# 20_V2X_MODEM.net
KiCad netlist of a schematic drawn in Altium Designer
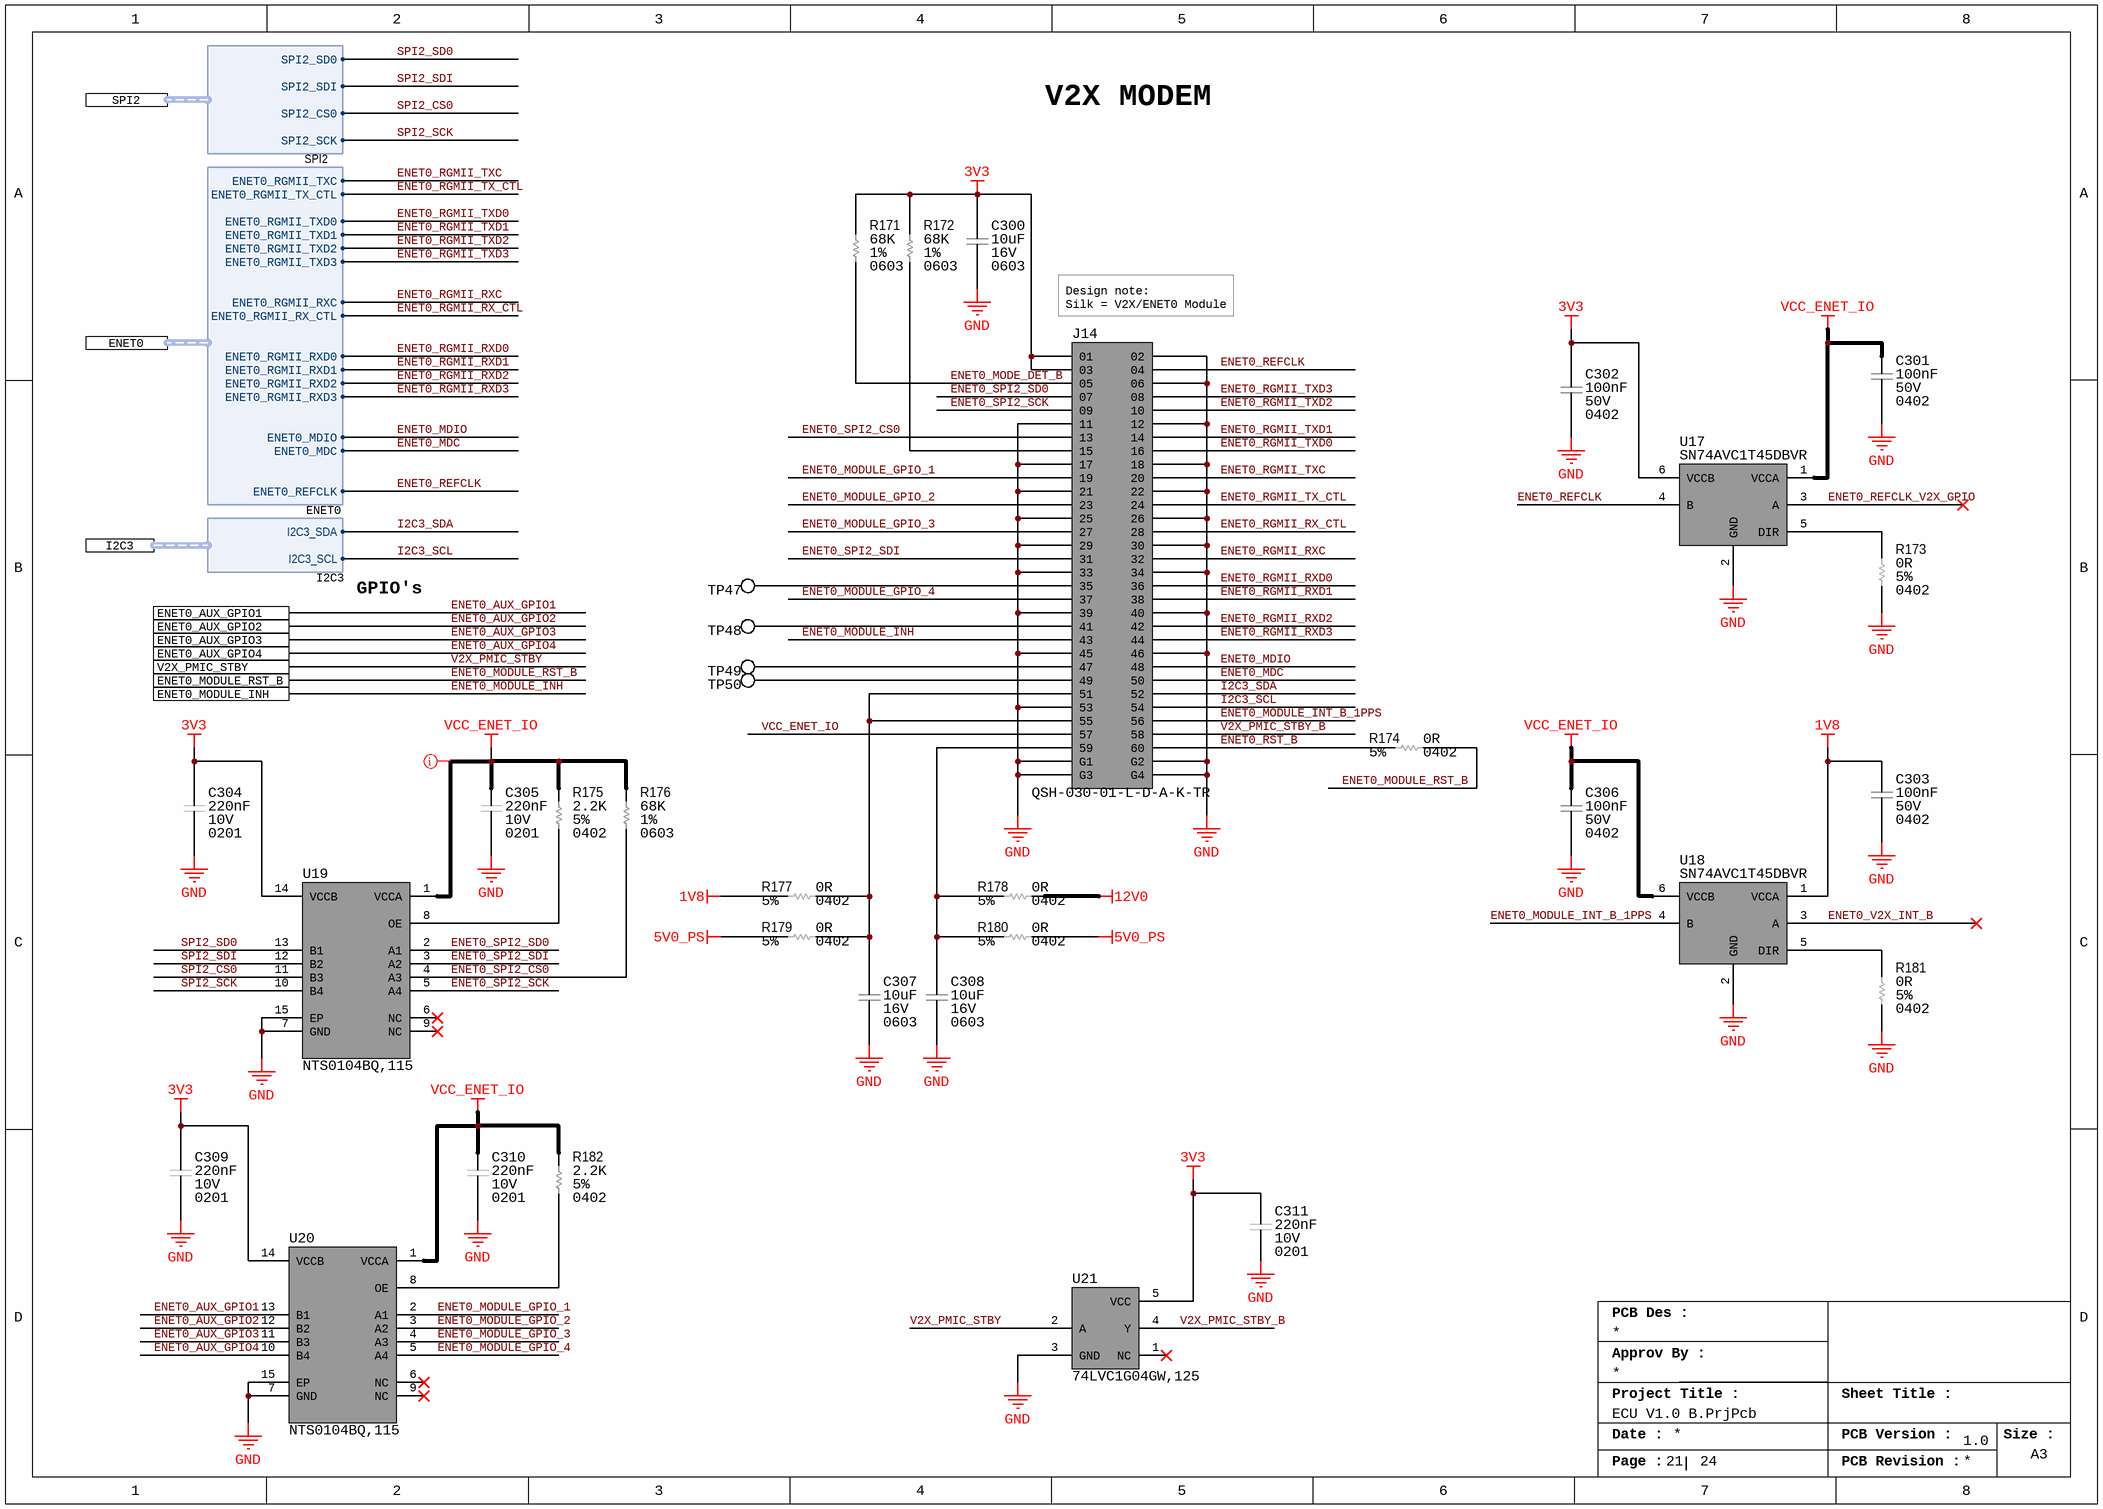
[diagram p0: 20_V2X_MODEM.SchDoc]

(export (version "E")
  (design (tool "Eeschema 10.0.6"))
  (components
    (comp (ref "C300")
      (value "GRM188R61C106MAALD")
      (footprint "CAP_0603_CAPC1608X08N")
      (description "0603 10 uF 16 V ±20% Tolerance X5R Multilayer Ceramic Chip Capacitor")
      (fields
        (field (name "MANUFACTURER") "Murata")
        (field (name "TOLERANCE") "20%")
        (field (name "VOLTAGE RATING") "16V")
        (field (name "CAPACITANCE") "10uF")
        (field (name "CASE/PACKAGE") "0603")
      )
      (libsource (lib "Electronic Devices_LIB") (part "CAP_10UF_16V_X5R_0603"))
    )
    (comp (ref "C301")
      (value "GRM155R71H104KE14D")
      (footprint "CAP_0402_CAPC1005X05N")
      (description "Multilayer Ceramic Capacitor, 0.1 uF, 16 V, ± 10%, X7R, 0402 [1005 Metric]")
      (fields
        (field (name "MANUFACTURER") "Murata")
        (field (name "TOLERANCE") "10%")
        (field (name "VOLTAGE RATING") "50V")
        (field (name "CAPACITANCE") "100nF")
        (field (name "CASE/PACKAGE") "0402")
      )
      (libsource (lib "Electronic Devices_LIB") (part "CAP_100NF_50V_X7R_0402"))
    )
    (comp (ref "C302")
      (value "GRM155R71H104KE14D")
      (footprint "CAP_0402_CAPC1005X05N")
      (description "Multilayer Ceramic Capacitor, 0.1 uF, 16 V, ± 10%, X7R, 0402 [1005 Metric]")
      (fields
        (field (name "MANUFACTURER") "Murata")
        (field (name "TOLERANCE") "10%")
        (field (name "VOLTAGE RATING") "50V")
        (field (name "CAPACITANCE") "100nF")
        (field (name "CASE/PACKAGE") "0402")
      )
      (libsource (lib "Electronic Devices_LIB") (part "CAP_100NF_50V_X7R_0402"))
    )
    (comp (ref "C303")
      (value "GRM155R71H104KE14D")
      (footprint "CAP_0402_CAPC1005X05N")
      (description "Multilayer Ceramic Capacitor, 0.1 uF, 16 V, ± 10%, X7R, 0402 [1005 Metric]")
      (fields
        (field (name "MANUFACTURER") "Murata")
        (field (name "TOLERANCE") "10%")
        (field (name "VOLTAGE RATING") "50V")
        (field (name "CAPACITANCE") "100nF")
        (field (name "CASE/PACKAGE") "0402")
      )
      (libsource (lib "Electronic Devices_LIB") (part "CAP_100NF_50V_X7R_0402"))
    )
    (comp (ref "C304")
      (value "LMK063BJ224MP-F")
      (footprint "CAP_0201_CAPC0603X03N")
      (description "Multilayer Ceramic Capacitors (High dielectric type), 10V, 0.22 uF, ± 20 %, 0201, X5R, RoHS")
      (fields
        (field (name "MANUFACTURER") "Taiyo Yuden")
        (field (name "TOLERANCE") "20%")
        (field (name "VOLTAGE RATING (DC)") "10V")
        (field (name "CAPACITANCE") "220nF")
        (field (name "CASE/PACKAGE") "0201")
      )
      (libsource (lib "Electronic Devices_LIB") (part "CAP_0.22UF_10V_X5R_0201"))
    )
    (comp (ref "C305")
      (value "LMK063BJ224MP-F")
      (footprint "CAP_0201_CAPC0603X03N")
      (description "Multilayer Ceramic Capacitors (High dielectric type), 10V, 0.22 uF, ± 20 %, 0201, X5R, RoHS")
      (fields
        (field (name "MANUFACTURER") "Taiyo Yuden")
        (field (name "TOLERANCE") "20%")
        (field (name "VOLTAGE RATING (DC)") "10V")
        (field (name "CAPACITANCE") "220nF")
        (field (name "CASE/PACKAGE") "0201")
      )
      (libsource (lib "Electronic Devices_LIB") (part "CAP_0.22UF_10V_X5R_0201"))
    )
    (comp (ref "C306")
      (value "GRM155R71H104KE14D")
      (footprint "CAP_0402_CAPC1005X05N")
      (description "Multilayer Ceramic Capacitor, 0.1 uF, 16 V, ± 10%, X7R, 0402 [1005 Metric]")
      (fields
        (field (name "MANUFACTURER") "Murata")
        (field (name "TOLERANCE") "10%")
        (field (name "VOLTAGE RATING") "50V")
        (field (name "CAPACITANCE") "100nF")
        (field (name "CASE/PACKAGE") "0402")
      )
      (libsource (lib "Electronic Devices_LIB") (part "CAP_100NF_50V_X7R_0402"))
    )
    (comp (ref "C307")
      (value "GRM188R61C106MAALD")
      (footprint "CAP_0603_CAPC1608X08N")
      (description "0603 10 uF 16 V ±20% Tolerance X5R Multilayer Ceramic Chip Capacitor")
      (fields
        (field (name "MANUFACTURER") "Murata")
        (field (name "TOLERANCE") "20%")
        (field (name "VOLTAGE RATING") "16V")
        (field (name "CAPACITANCE") "10uF")
        (field (name "CASE/PACKAGE") "0603")
      )
      (libsource (lib "Electronic Devices_LIB") (part "CAP_10UF_16V_X5R_0603"))
    )
    (comp (ref "C308")
      (value "GRM188R61C106MAALD")
      (footprint "CAP_0603_CAPC1608X08N")
      (description "0603 10 uF 16 V ±20% Tolerance X5R Multilayer Ceramic Chip Capacitor")
      (fields
        (field (name "MANUFACTURER") "Murata")
        (field (name "TOLERANCE") "20%")
        (field (name "VOLTAGE RATING") "16V")
        (field (name "CAPACITANCE") "10uF")
        (field (name "CASE/PACKAGE") "0603")
      )
      (libsource (lib "Electronic Devices_LIB") (part "CAP_10UF_16V_X5R_0603"))
    )
    (comp (ref "C309")
      (value "LMK063BJ224MP-F")
      (footprint "CAP_0201_CAPC0603X03N")
      (description "Multilayer Ceramic Capacitors (High dielectric type), 10V, 0.22 uF, ± 20 %, 0201, X5R, RoHS")
      (fields
        (field (name "MANUFACTURER") "Taiyo Yuden")
        (field (name "TOLERANCE") "20%")
        (field (name "VOLTAGE RATING (DC)") "10V")
        (field (name "CAPACITANCE") "220nF")
        (field (name "CASE/PACKAGE") "0201")
      )
      (libsource (lib "Electronic Devices_LIB") (part "CAP_0.22UF_10V_X5R_0201"))
    )
    (comp (ref "C310")
      (value "LMK063BJ224MP-F")
      (footprint "CAP_0201_CAPC0603X03N")
      (description "Multilayer Ceramic Capacitors (High dielectric type), 10V, 0.22 uF, ± 20 %, 0201, X5R, RoHS")
      (fields
        (field (name "MANUFACTURER") "Taiyo Yuden")
        (field (name "TOLERANCE") "20%")
        (field (name "VOLTAGE RATING (DC)") "10V")
        (field (name "CAPACITANCE") "220nF")
        (field (name "CASE/PACKAGE") "0201")
      )
      (libsource (lib "Electronic Devices_LIB") (part "CAP_0.22UF_10V_X5R_0201"))
    )
    (comp (ref "C311")
      (value "LMK063BJ224MP-F")
      (footprint "CAP_0201_CAPC0603X03N")
      (description "Multilayer Ceramic Capacitors (High dielectric type), 10V, 0.22 uF, ± 20 %, 0201, X5R, RoHS")
      (fields
        (field (name "MANUFACTURER") "Taiyo Yuden")
        (field (name "TOLERANCE") "20%")
        (field (name "VOLTAGE RATING (DC)") "10V")
        (field (name "CAPACITANCE") "220nF")
        (field (name "CASE/PACKAGE") "0201")
      )
      (libsource (lib "Electronic Devices_LIB") (part "CAP_0.22UF_10V_X5R_0201"))
    )
    (comp (ref "J14")
      (value "QSH-030-01-L-D-A-K-TR")
      (footprint "SAMTEC_QSH-030-01-X-D-A-XX")
      (description "Board to Board & Mezzanine Connectors 0.50 mm Q Strip High-Speed Ground Plane Socket Strip")
      (fields (field (name "MANUFACTURER") "Samtec"))
      (libsource (lib "Electronic Devices_LIB") (part "CONN_MEZZANINE_60P_0.5mm_QSH-030-01-L-D-A-K-TR"))
    )
    (comp (ref "R171")
      (value "RC0603FR-0768KL")
      (footprint "RES_0603_RESC1608X04N")
      (description "SMD Chip Resistor, 68 kOhm, ± 1%, 100 mW, 0603 [1608 Metric], Thick Film, General Purpose")
      (fields
        (field (name "MANUFACTURER") "Yageo")
        (field (name "TOLERANCE") "1%")
        (field (name "RESISTANCE") "68K")
        (field (name "CASE/PACKAGE") "0603")
      )
      (libsource (lib "Electronic Devices_LIB") (part "RES_68K_1%_100mW_0603"))
    )
    (comp (ref "R172")
      (value "RC0603FR-0768KL")
      (footprint "RES_0603_RESC1608X04N")
      (description "SMD Chip Resistor, 68 kOhm, ± 1%, 100 mW, 0603 [1608 Metric], Thick Film, General Purpose")
      (fields
        (field (name "MANUFACTURER") "Yageo")
        (field (name "TOLERANCE") "1%")
        (field (name "RESISTANCE") "68K")
        (field (name "CASE/PACKAGE") "0603")
      )
      (libsource (lib "Electronic Devices_LIB") (part "RES_68K_1%_100mW_0603"))
    )
    (comp (ref "R173")
      (value "ERJ-2GE0R00X")
      (footprint "RES_0402_RESC1005X04N")
      (description "SMD Chip Resistor, Jumper, 0 ohm, 100 mW, 0402 [1005 Metric], Thick Film, General Purpose")
      (fields
        (field (name "MANUFACTURER") "Panasonic")
        (field (name "CASE CODE (IMPERIAL)") "0402")
        (field (name "TOLERANCE") "5%")
        (field (name "RESISTANCE") "0R")
      )
      (libsource (lib "Electronic Devices_LIB") (part "RES_0R_5%_100mW_0402"))
    )
    (comp (ref "R174")
      (value "ERJ-2GE0R00X")
      (footprint "RES_0402_RESC1005X04N")
      (description "SMD Chip Resistor, Jumper, 0 ohm, 100 mW, 0402 [1005 Metric], Thick Film, General Purpose")
      (fields
        (field (name "MANUFACTURER") "Panasonic")
        (field (name "CASE CODE (IMPERIAL)") "0402")
        (field (name "TOLERANCE") "5%")
        (field (name "RESISTANCE") "0R")
      )
      (libsource (lib "Electronic Devices_LIB") (part "RES_0R_5%_100mW_0402"))
    )
    (comp (ref "R175")
      (value "RC0402JR-072K2L")
      (footprint "RES_0402_RESC1005X04N")
      (description "SMD Chip Resistor, 2.2 kOhm, ± 5%, 63 mW, 0402 [1005 Metric], Thick Film, General Purpose")
      (fields
        (field (name "MANUFACTURER") "Yageo")
        (field (name "TOLERANCE") "5%")
        (field (name "RESISTANCE") "2.2K")
        (field (name "CASE/PACKAGE") "0402")
      )
      (libsource (lib "Electronic Devices_LIB") (part "RES_2.2K_5%_63mW_0402"))
    )
    (comp (ref "R176")
      (value "RC0603FR-0768KL")
      (footprint "RES_0603_RESC1608X04N")
      (description "SMD Chip Resistor, 68 kOhm, ± 1%, 100 mW, 0603 [1608 Metric], Thick Film, General Purpose")
      (fields
        (field (name "MANUFACTURER") "Yageo")
        (field (name "TOLERANCE") "1%")
        (field (name "RESISTANCE") "68K")
        (field (name "CASE/PACKAGE") "0603")
      )
      (libsource (lib "Electronic Devices_LIB") (part "RES_68K_1%_100mW_0603"))
    )
    (comp (ref "R177")
      (value "ERJ-2GE0R00X")
      (footprint "RES_0402_RESC1005X04N")
      (description "SMD Chip Resistor, Jumper, 0 ohm, 100 mW, 0402 [1005 Metric], Thick Film, General Purpose")
      (fields
        (field (name "MANUFACTURER") "Panasonic")
        (field (name "CASE CODE (IMPERIAL)") "0402")
        (field (name "TOLERANCE") "5%")
        (field (name "RESISTANCE") "0R")
      )
      (libsource (lib "Electronic Devices_LIB") (part "RES_0R_5%_100mW_0402"))
    )
    (comp (ref "R178")
      (value "ERJ-2GE0R00X")
      (footprint "RES_0402_RESC1005X04N")
      (description "SMD Chip Resistor, Jumper, 0 ohm, 100 mW, 0402 [1005 Metric], Thick Film, General Purpose")
      (fields
        (field (name "MANUFACTURER") "Panasonic")
        (field (name "CASE CODE (IMPERIAL)") "0402")
        (field (name "TOLERANCE") "5%")
        (field (name "RESISTANCE") "0R")
      )
      (libsource (lib "Electronic Devices_LIB") (part "RES_0R_5%_100mW_0402"))
    )
    (comp (ref "R179")
      (value "ERJ-2GE0R00X")
      (footprint "RES_0402_RESC1005X04N")
      (description "SMD Chip Resistor, Jumper, 0 ohm, 100 mW, 0402 [1005 Metric], Thick Film, General Purpose")
      (fields
        (field (name "MANUFACTURER") "Panasonic")
        (field (name "CASE CODE (IMPERIAL)") "0402")
        (field (name "TOLERANCE") "5%")
        (field (name "RESISTANCE") "0R")
      )
      (libsource (lib "Electronic Devices_LIB") (part "RES_0R_5%_100mW_0402"))
    )
    (comp (ref "R180")
      (value "ERJ-2GE0R00X")
      (footprint "RES_0402_RESC1005X04N")
      (description "SMD Chip Resistor, Jumper, 0 ohm, 100 mW, 0402 [1005 Metric], Thick Film, General Purpose")
      (fields
        (field (name "MANUFACTURER") "Panasonic")
        (field (name "CASE CODE (IMPERIAL)") "0402")
        (field (name "TOLERANCE") "5%")
        (field (name "RESISTANCE") "0R")
      )
      (libsource (lib "Electronic Devices_LIB") (part "RES_0R_5%_100mW_0402"))
    )
    (comp (ref "R181")
      (value "ERJ-2GE0R00X")
      (footprint "RES_0402_RESC1005X04N")
      (description "SMD Chip Resistor, Jumper, 0 ohm, 100 mW, 0402 [1005 Metric], Thick Film, General Purpose")
      (fields
        (field (name "MANUFACTURER") "Panasonic")
        (field (name "CASE CODE (IMPERIAL)") "0402")
        (field (name "TOLERANCE") "5%")
        (field (name "RESISTANCE") "0R")
      )
      (libsource (lib "Electronic Devices_LIB") (part "RES_0R_5%_100mW_0402"))
    )
    (comp (ref "R182")
      (value "RC0402JR-072K2L")
      (footprint "RES_0402_RESC1005X04N")
      (description "SMD Chip Resistor, 2.2 kOhm, ± 5%, 63 mW, 0402 [1005 Metric], Thick Film, General Purpose")
      (fields
        (field (name "MANUFACTURER") "Yageo")
        (field (name "TOLERANCE") "5%")
        (field (name "RESISTANCE") "2.2K")
        (field (name "CASE/PACKAGE") "0402")
      )
      (libsource (lib "Electronic Devices_LIB") (part "RES_2.2K_5%_63mW_0402"))
    )
    (comp (ref "TP47")
      (value "NO COMPONENT")
      (footprint "TP_PAD_0.5MM_SMD_ROUND")
      (description "Test Point, SMD pad, round, 1.5mm, 1.6mm, 3mm diameter")
      (libsource (lib "Electronic Devices_LIB") (part "TP_PAD_SMD_SMALL"))
    )
    (comp (ref "TP48")
      (value "NO COMPONENT")
      (footprint "TP_PAD_0.5MM_SMD_ROUND")
      (description "Test Point, SMD pad, round, 1.5mm, 1.6mm, 3mm diameter")
      (libsource (lib "Electronic Devices_LIB") (part "TP_PAD_SMD_SMALL"))
    )
    (comp (ref "TP49")
      (value "NO COMPONENT")
      (footprint "TP_PAD_0.5MM_SMD_ROUND")
      (description "Test Point, SMD pad, round, 1.5mm, 1.6mm, 3mm diameter")
      (libsource (lib "Electronic Devices_LIB") (part "TP_PAD_SMD_SMALL"))
    )
    (comp (ref "TP50")
      (value "NO COMPONENT")
      (footprint "TP_PAD_0.5MM_SMD_ROUND")
      (description "Test Point, SMD pad, round, 1.5mm, 1.6mm, 3mm diameter")
      (libsource (lib "Electronic Devices_LIB") (part "TP_PAD_SMD_SMALL"))
    )
    (comp (ref "U17")
      (value "SN74AVC1T45DBVR")
      (footprint "SOT95P280X145-6N")
      (description "1.2V~3.6V 1 1 1.2V~3.6V 500Mbps SOT-23-6 Translators / Level Shifters ROHS")
      (fields (field (name "MANUFACTURER") "Texas Instruments"))
      (libsource (lib "Electronic Devices_LIB") (part "IC_LEVEL_TRANSLATE_1CH_SN74AVC1T45DBVR"))
    )
    (comp (ref "U18")
      (value "SN74AVC1T45DBVR")
      (footprint "SOT95P280X145-6N")
      (description "1.2V~3.6V 1 1 1.2V~3.6V 500Mbps SOT-23-6 Translators / Level Shifters ROHS")
      (fields (field (name "MANUFACTURER") "Texas Instruments"))
      (libsource (lib "Electronic Devices_LIB") (part "IC_LEVEL_TRANSLATE_1CH_SN74AVC1T45DBVR"))
    )
    (comp (ref "U19")
      (value "NTS0104BQ,115")
      (footprint "QFN50P300X250X100-15N")
      (description "Voltage Level Translator Bidirectional 1 Circuit 4 Channel 50Mbps 14-DHVQFN (2.5x3)")
      (fields (field (name "MANUFACTURER") "NXP Semiconductors"))
      (libsource (lib "Electronic Devices_LIB") (part "IC_LEVEL_TRASLATE_4CH_NTS0104BQ,115"))
    )
    (comp (ref "U20")
      (value "NTS0104BQ,115")
      (footprint "QFN50P300X250X100-15N")
      (description "Voltage Level Translator Bidirectional 1 Circuit 4 Channel 50Mbps 14-DHVQFN (2.5x3)")
      (fields (field (name "MANUFACTURER") "NXP Semiconductors"))
      (libsource (lib "Electronic Devices_LIB") (part "IC_LEVEL_TRASLATE_4CH_NTS0104BQ,115"))
    )
    (comp (ref "U21")
      (value "74LVC1G04GW,125")
      (footprint "SOT65P210X110-5N")
      (description "74LVC Series 5.5 V Surface Mount Single Inverting Buffer - TSSOP-5")
      (fields (field (name "MANUFACTURER") "Nexperia"))
      (libsource (lib "Electronic Devices_LIB") (part "IC_INVERTER_1CH_74LVC1G04GW,125"))
    )
  )
  (nets
    (net (code "4") (name "/ENET0_AUX_GPIO1") (class "Default")
      (node (ref "U20") (pin "13") (pinfunction "B1_13") (pintype "passive"))
    )
    (net (code "5") (name "/ENET0_AUX_GPIO2") (class "Default")
      (node (ref "U20") (pin "12") (pinfunction "B2_12") (pintype "passive"))
    )
    (net (code "6") (name "/ENET0_AUX_GPIO3") (class "Default")
      (node (ref "U20") (pin "11") (pinfunction "B3_11") (pintype "passive"))
    )
    (net (code "7") (name "/ENET0_AUX_GPIO4") (class "Default")
      (node (ref "U20") (pin "10") (pinfunction "B4_10") (pintype "passive"))
    )
    (net (code "8") (name "/ENET0_MDC") (class "Default")
      (node (ref "J14") (pin "50") (pinfunction "50_50") (pintype "passive"))
    )
    (net (code "9") (name "/ENET0_MDIO") (class "Default")
      (node (ref "J14") (pin "48") (pinfunction "48_48") (pintype "passive"))
    )
    (net (code "10") (name "/ENET0_MODE_DET_B") (class "Default")
      (node (ref "J14") (pin "05") (pinfunction "05_05") (pintype "passive"))
      (node (ref "R171") (pin "1") (pinfunction "1_1") (pintype "passive"))
    )
    (net (code "11") (name "/ENET0_MODULE_GPIO_1") (class "Default")
      (node (ref "J14") (pin "19") (pinfunction "19_19") (pintype "passive"))
      (node (ref "U20") (pin "2") (pinfunction "A1_2") (pintype "passive"))
    )
    (net (code "12") (name "/ENET0_MODULE_GPIO_2") (class "Default")
      (node (ref "J14") (pin "23") (pinfunction "23_23") (pintype "passive"))
      (node (ref "U20") (pin "3") (pinfunction "A2_3") (pintype "passive"))
    )
    (net (code "13") (name "/ENET0_MODULE_GPIO_3") (class "Default")
      (node (ref "J14") (pin "27") (pinfunction "27_27") (pintype "passive"))
      (node (ref "U20") (pin "4") (pinfunction "A3_4") (pintype "passive"))
    )
    (net (code "14") (name "/ENET0_MODULE_GPIO_4") (class "Default")
      (node (ref "J14") (pin "37") (pinfunction "37_37") (pintype "passive"))
      (node (ref "U20") (pin "5") (pinfunction "A4_5") (pintype "passive"))
    )
    (net (code "15") (name "/ENET0_MODULE_INH") (class "Default")
      (node (ref "J14") (pin "43") (pinfunction "43_43") (pintype "passive"))
    )
    (net (code "16") (name "/ENET0_MODULE_INT_B_1PPS") (class "Default")
      (node (ref "J14") (pin "56") (pinfunction "56_56") (pintype "passive"))
      (node (ref "U18") (pin "4") (pinfunction "B_4") (pintype "passive"))
    )
    (net (code "17") (name "/ENET0_MODULE_RST_B") (class "Default")
      (node (ref "R174") (pin "2") (pinfunction "2_2") (pintype "passive"))
    )
    (net (code "18") (name "/ENET0_REFCLK") (class "Default")
      (node (ref "J14") (pin "04") (pinfunction "04_04") (pintype "passive"))
      (node (ref "U17") (pin "4") (pinfunction "B_4") (pintype "passive"))
    )
    (net (code "19") (name "/ENET0_REFCLK_V2X_GPIO") (class "Default")
      (node (ref "U17") (pin "3") (pinfunction "A_3") (pintype "passive+no_connect"))
    )
    (net (code "20") (name "/ENET0_RGMII_RXC") (class "Default")
      (node (ref "J14") (pin "32") (pinfunction "32_32") (pintype "passive"))
    )
    (net (code "21") (name "/ENET0_RGMII_RXD0") (class "Default")
      (node (ref "J14") (pin "36") (pinfunction "36_36") (pintype "passive"))
    )
    (net (code "22") (name "/ENET0_RGMII_RXD1") (class "Default")
      (node (ref "J14") (pin "38") (pinfunction "38_38") (pintype "passive"))
    )
    (net (code "23") (name "/ENET0_RGMII_RXD2") (class "Default")
      (node (ref "J14") (pin "42") (pinfunction "42_42") (pintype "passive"))
    )
    (net (code "24") (name "/ENET0_RGMII_RXD3") (class "Default")
      (node (ref "J14") (pin "44") (pinfunction "44_44") (pintype "passive"))
    )
    (net (code "25") (name "/ENET0_RGMII_RX_CTL") (class "Default")
      (node (ref "J14") (pin "28") (pinfunction "28_28") (pintype "passive"))
    )
    (net (code "26") (name "/ENET0_RGMII_TXC") (class "Default")
      (node (ref "J14") (pin "20") (pinfunction "20_20") (pintype "passive"))
    )
    (net (code "27") (name "/ENET0_RGMII_TXD0") (class "Default")
      (node (ref "J14") (pin "16") (pinfunction "16_16") (pintype "passive"))
    )
    (net (code "28") (name "/ENET0_RGMII_TXD1") (class "Default")
      (node (ref "J14") (pin "14") (pinfunction "14_14") (pintype "passive"))
    )
    (net (code "29") (name "/ENET0_RGMII_TXD2") (class "Default")
      (node (ref "J14") (pin "10") (pinfunction "10_10") (pintype "passive"))
    )
    (net (code "30") (name "/ENET0_RGMII_TXD3") (class "Default")
      (node (ref "J14") (pin "08") (pinfunction "08_08") (pintype "passive"))
    )
    (net (code "31") (name "/ENET0_RGMII_TX_CTL") (class "Default")
      (node (ref "J14") (pin "24") (pinfunction "24_24") (pintype "passive"))
    )
    (net (code "32") (name "/ENET0_RST_B") (class "Default")
      (node (ref "J14") (pin "60") (pinfunction "60_60") (pintype "passive"))
      (node (ref "R174") (pin "1") (pinfunction "1_1") (pintype "passive"))
    )
    (net (code "33") (name "/ENET0_SPI2_CS0") (class "Default")
      (node (ref "J14") (pin "13") (pinfunction "13_13") (pintype "passive"))
      (node (ref "R176") (pin "1") (pinfunction "1_1") (pintype "passive"))
      (node (ref "U19") (pin "4") (pinfunction "A3_4") (pintype "passive"))
    )
    (net (code "34") (name "/ENET0_SPI2_SCK") (class "Default")
      (node (ref "J14") (pin "09") (pinfunction "09_09") (pintype "passive"))
      (node (ref "U19") (pin "5") (pinfunction "A4_5") (pintype "passive"))
    )
    (net (code "35") (name "/ENET0_SPI2_SD0") (class "Default")
      (node (ref "J14") (pin "07") (pinfunction "07_07") (pintype "passive"))
      (node (ref "U19") (pin "2") (pinfunction "A1_2") (pintype "passive"))
    )
    (net (code "36") (name "/ENET0_SPI2_SDI") (class "Default")
      (node (ref "J14") (pin "31") (pinfunction "31_31") (pintype "passive"))
      (node (ref "U19") (pin "3") (pinfunction "A2_3") (pintype "passive"))
    )
    (net (code "37") (name "/ENET0_V2X_INT_B") (class "Default")
      (node (ref "U18") (pin "3") (pinfunction "A_3") (pintype "passive+no_connect"))
    )
    (net (code "38") (name "/I2C3_SCL") (class "Default")
      (node (ref "J14") (pin "54") (pinfunction "54_54") (pintype "passive"))
    )
    (net (code "39") (name "/I2C3_SDA") (class "Default")
      (node (ref "J14") (pin "52") (pinfunction "52_52") (pintype "passive"))
    )
    (net (code "40") (name "/SPI2_CS0") (class "Default")
      (node (ref "U19") (pin "11") (pinfunction "B3_11") (pintype "passive"))
    )
    (net (code "41") (name "/SPI2_SCK") (class "Default")
      (node (ref "U19") (pin "10") (pinfunction "B4_10") (pintype "passive"))
    )
    (net (code "42") (name "/SPI2_SD0") (class "Default")
      (node (ref "U19") (pin "13") (pinfunction "B1_13") (pintype "passive"))
    )
    (net (code "43") (name "/SPI2_SDI") (class "Default")
      (node (ref "U19") (pin "12") (pinfunction "B2_12") (pintype "passive"))
    )
    (net (code "44") (name "/V2X_PMIC_STBY") (class "Default")
      (node (ref "U21") (pin "2") (pinfunction "A_2") (pintype "passive"))
    )
    (net (code "45") (name "/V2X_PMIC_STBY_B") (class "Default")
      (node (ref "J14") (pin "58") (pinfunction "58_58") (pintype "passive"))
      (node (ref "U21") (pin "4") (pinfunction "Y_4") (pintype "passive"))
    )
    (net (code "49") (name "1V8") (class "Default")
      (node (ref "C303") (pin "2") (pinfunction "2_2") (pintype "passive"))
      (node (ref "R177") (pin "1") (pinfunction "1_1") (pintype "passive"))
      (node (ref "U18") (pin "1") (pinfunction "VCCA_1") (pintype "power_in"))
    )
    (net (code "50") (name "3V3") (class "Default")
      (node (ref "C300") (pin "2") (pinfunction "2_2") (pintype "passive"))
      (node (ref "C302") (pin "2") (pinfunction "2_2") (pintype "passive"))
      (node (ref "C304") (pin "1") (pinfunction "1_1") (pintype "passive"))
      (node (ref "C309") (pin "1") (pinfunction "1_1") (pintype "passive"))
      (node (ref "C311") (pin "1") (pinfunction "1_1") (pintype "passive"))
      (node (ref "J14") (pin "01") (pinfunction "01_01") (pintype "passive"))
      (node (ref "J14") (pin "03") (pinfunction "03_03") (pintype "passive"))
      (node (ref "R171") (pin "2") (pinfunction "2_2") (pintype "passive"))
      (node (ref "R172") (pin "2") (pinfunction "2_2") (pintype "passive"))
      (node (ref "U17") (pin "6") (pinfunction "VCCB_6") (pintype "power_in"))
      (node (ref "U19") (pin "14") (pinfunction "VCCB_14") (pintype "power_in"))
      (node (ref "U20") (pin "14") (pinfunction "VCCB_14") (pintype "power_in"))
      (node (ref "U21") (pin "5") (pinfunction "VCC_5") (pintype "power_in"))
    )
    (net (code "51") (name "5V0_PS") (class "Default")
      (node (ref "R179") (pin "1") (pinfunction "1_1") (pintype "passive"))
      (node (ref "R180") (pin "2") (pinfunction "2_2") (pintype "passive"))
    )
    (net (code "52") (name "12V0") (class "Default")
      (node (ref "R178") (pin "2") (pinfunction "2_2") (pintype "passive"))
    )
    (net (code "53") (name "GND") (class "Default")
      (node (ref "C300") (pin "1") (pinfunction "1_1") (pintype "passive"))
      (node (ref "C301") (pin "1") (pinfunction "1_1") (pintype "passive"))
      (node (ref "C302") (pin "1") (pinfunction "1_1") (pintype "passive"))
      (node (ref "C303") (pin "1") (pinfunction "1_1") (pintype "passive"))
      (node (ref "C304") (pin "2") (pinfunction "2_2") (pintype "passive"))
      (node (ref "C305") (pin "2") (pinfunction "2_2") (pintype "passive"))
      (node (ref "C306") (pin "1") (pinfunction "1_1") (pintype "passive"))
      (node (ref "C307") (pin "1") (pinfunction "1_1") (pintype "passive"))
      (node (ref "C308") (pin "1") (pinfunction "1_1") (pintype "passive"))
      (node (ref "C309") (pin "2") (pinfunction "2_2") (pintype "passive"))
      (node (ref "C310") (pin "2") (pinfunction "2_2") (pintype "passive"))
      (node (ref "C311") (pin "2") (pinfunction "2_2") (pintype "passive"))
      (node (ref "J14") (pin "02") (pinfunction "02_02") (pintype "passive"))
      (node (ref "J14") (pin "06") (pinfunction "06_06") (pintype "passive"))
      (node (ref "J14") (pin "11") (pinfunction "11_11") (pintype "passive"))
      (node (ref "J14") (pin "12") (pinfunction "12_12") (pintype "passive"))
      (node (ref "J14") (pin "17") (pinfunction "17_17") (pintype "passive"))
      (node (ref "J14") (pin "18") (pinfunction "18_18") (pintype "passive"))
      (node (ref "J14") (pin "21") (pinfunction "21_21") (pintype "passive"))
      (node (ref "J14") (pin "22") (pinfunction "22_22") (pintype "passive"))
      (node (ref "J14") (pin "25") (pinfunction "25_25") (pintype "passive"))
      (node (ref "J14") (pin "26") (pinfunction "26_26") (pintype "passive"))
      (node (ref "J14") (pin "29") (pinfunction "29_29") (pintype "passive"))
      (node (ref "J14") (pin "30") (pinfunction "30_30") (pintype "passive"))
      (node (ref "J14") (pin "33") (pinfunction "33_33") (pintype "passive"))
      (node (ref "J14") (pin "34") (pinfunction "34_34") (pintype "passive"))
      (node (ref "J14") (pin "39") (pinfunction "39_39") (pintype "passive"))
      (node (ref "J14") (pin "40") (pinfunction "40_40") (pintype "passive"))
      (node (ref "J14") (pin "45") (pinfunction "45_45") (pintype "passive"))
      (node (ref "J14") (pin "46") (pinfunction "46_46") (pintype "passive"))
      (node (ref "J14") (pin "53") (pinfunction "53_53") (pintype "passive"))
      (node (ref "J14") (pin "G1") (pinfunction "G1_G1") (pintype "power_in"))
      (node (ref "J14") (pin "G2") (pinfunction "G2_G2") (pintype "power_in"))
      (node (ref "J14") (pin "G3") (pinfunction "G3_G3") (pintype "power_in"))
      (node (ref "J14") (pin "G4") (pinfunction "G4_G4") (pintype "power_in"))
      (node (ref "R173") (pin "1") (pinfunction "1_1") (pintype "passive"))
      (node (ref "R181") (pin "1") (pinfunction "1_1") (pintype "passive"))
      (node (ref "U17") (pin "2") (pinfunction "GND_2") (pintype "power_in"))
      (node (ref "U18") (pin "2") (pinfunction "GND_2") (pintype "power_in"))
      (node (ref "U19") (pin "15") (pinfunction "EP_15") (pintype "passive"))
      (node (ref "U19") (pin "7") (pinfunction "GND_7") (pintype "power_in"))
      (node (ref "U20") (pin "15") (pinfunction "EP_15") (pintype "passive"))
      (node (ref "U20") (pin "7") (pinfunction "GND_7") (pintype "power_in"))
      (node (ref "U21") (pin "3") (pinfunction "GND_3") (pintype "power_in"))
    )
    (net (code "54") (name "Net-(C307-Pad2)") (class "Default")
      (node (ref "C307") (pin "2") (pinfunction "2_2") (pintype "passive"))
      (node (ref "J14") (pin "51") (pinfunction "51_51") (pintype "passive"))
      (node (ref "J14") (pin "55") (pinfunction "55_55") (pintype "passive"))
      (node (ref "R177") (pin "2") (pinfunction "2_2") (pintype "passive"))
      (node (ref "R179") (pin "2") (pinfunction "2_2") (pintype "passive"))
    )
    (net (code "55") (name "Net-(C308-Pad2)") (class "Default")
      (node (ref "C308") (pin "2") (pinfunction "2_2") (pintype "passive"))
      (node (ref "J14") (pin "59") (pinfunction "59_59") (pintype "passive"))
      (node (ref "R178") (pin "1") (pinfunction "1_1") (pintype "passive"))
      (node (ref "R180") (pin "1") (pinfunction "1_1") (pintype "passive"))
    )
    (net (code "56") (name "Net-(J14-Pad15)") (class "Default")
      (node (ref "J14") (pin "15") (pinfunction "15_15") (pintype "passive"))
      (node (ref "R172") (pin "1") (pinfunction "1_1") (pintype "passive"))
    )
    (net (code "57") (name "Net-(J14-Pad35)") (class "Default")
      (node (ref "J14") (pin "35") (pinfunction "35_35") (pintype "passive"))
      (node (ref "TP47") (pin "1") (pinfunction "1_1") (pintype "passive"))
    )
    (net (code "58") (name "Net-(J14-Pad41)") (class "Default")
      (node (ref "J14") (pin "41") (pinfunction "41_41") (pintype "passive"))
      (node (ref "TP48") (pin "1") (pinfunction "1_1") (pintype "passive"))
    )
    (net (code "59") (name "Net-(J14-Pad47)") (class "Default")
      (node (ref "J14") (pin "47") (pinfunction "47_47") (pintype "passive"))
      (node (ref "TP49") (pin "1") (pinfunction "1_1") (pintype "passive"))
    )
    (net (code "60") (name "Net-(J14-Pad49)") (class "Default")
      (node (ref "J14") (pin "49") (pinfunction "49_49") (pintype "passive"))
      (node (ref "TP50") (pin "1") (pinfunction "1_1") (pintype "passive"))
    )
    (net (code "61") (name "Net-(U17-DIR)") (class "Default")
      (node (ref "R173") (pin "2") (pinfunction "2_2") (pintype "passive"))
      (node (ref "U17") (pin "5") (pinfunction "DIR_5") (pintype "passive"))
    )
    (net (code "62") (name "Net-(U18-DIR)") (class "Default")
      (node (ref "R181") (pin "2") (pinfunction "2_2") (pintype "passive"))
      (node (ref "U18") (pin "5") (pinfunction "DIR_5") (pintype "passive"))
    )
    (net (code "63") (name "Net-(U19-OE)") (class "Default")
      (node (ref "R175") (pin "1") (pinfunction "1_1") (pintype "passive"))
      (node (ref "U19") (pin "8") (pinfunction "OE_8") (pintype "passive"))
    )
    (net (code "64") (name "Net-(U20-OE)") (class "Default")
      (node (ref "R182") (pin "1") (pinfunction "1_1") (pintype "passive"))
      (node (ref "U20") (pin "8") (pinfunction "OE_8") (pintype "passive"))
    )
    (net (code "65") (name "VCC_ENET_IO") (class "Default")
      (node (ref "C301") (pin "2") (pinfunction "2_2") (pintype "passive"))
      (node (ref "C305") (pin "1") (pinfunction "1_1") (pintype "passive"))
      (node (ref "C306") (pin "2") (pinfunction "2_2") (pintype "passive"))
      (node (ref "C310") (pin "1") (pinfunction "1_1") (pintype "passive"))
      (node (ref "J14") (pin "57") (pinfunction "57_57") (pintype "passive"))
      (node (ref "R175") (pin "2") (pinfunction "2_2") (pintype "passive"))
      (node (ref "R176") (pin "2") (pinfunction "2_2") (pintype "passive"))
      (node (ref "R182") (pin "2") (pinfunction "2_2") (pintype "passive"))
      (node (ref "U17") (pin "1") (pinfunction "VCCA_1") (pintype "power_in"))
      (node (ref "U18") (pin "6") (pinfunction "VCCB_6") (pintype "power_in"))
      (node (ref "U19") (pin "1") (pinfunction "VCCA_1") (pintype "power_in"))
      (node (ref "U20") (pin "1") (pinfunction "VCCA_1") (pintype "power_in"))
    )
    (net (code "66") (name "unconnected-(U19-NC-Pad6)") (class "Default")
      (node (ref "U19") (pin "6") (pinfunction "NC_6") (pintype "passive+no_connect"))
    )
    (net (code "67") (name "unconnected-(U19-NC-Pad9)") (class "Default")
      (node (ref "U19") (pin "9") (pinfunction "NC_9") (pintype "passive+no_connect"))
    )
    (net (code "68") (name "unconnected-(U20-NC-Pad6)") (class "Default")
      (node (ref "U20") (pin "6") (pinfunction "NC_6") (pintype "passive+no_connect"))
    )
    (net (code "69") (name "unconnected-(U20-NC-Pad9)") (class "Default")
      (node (ref "U20") (pin "9") (pinfunction "NC_9") (pintype "passive+no_connect"))
    )
    (net (code "70") (name "unconnected-(U21-NC-Pad1)") (class "Default")
      (node (ref "U21") (pin "1") (pinfunction "NC_1") (pintype "passive+no_connect"))
    )
  )
)
